# attinier84-motherboard-mk-2_0.net
KiCad netlist of a schematic drawn in EAGLE
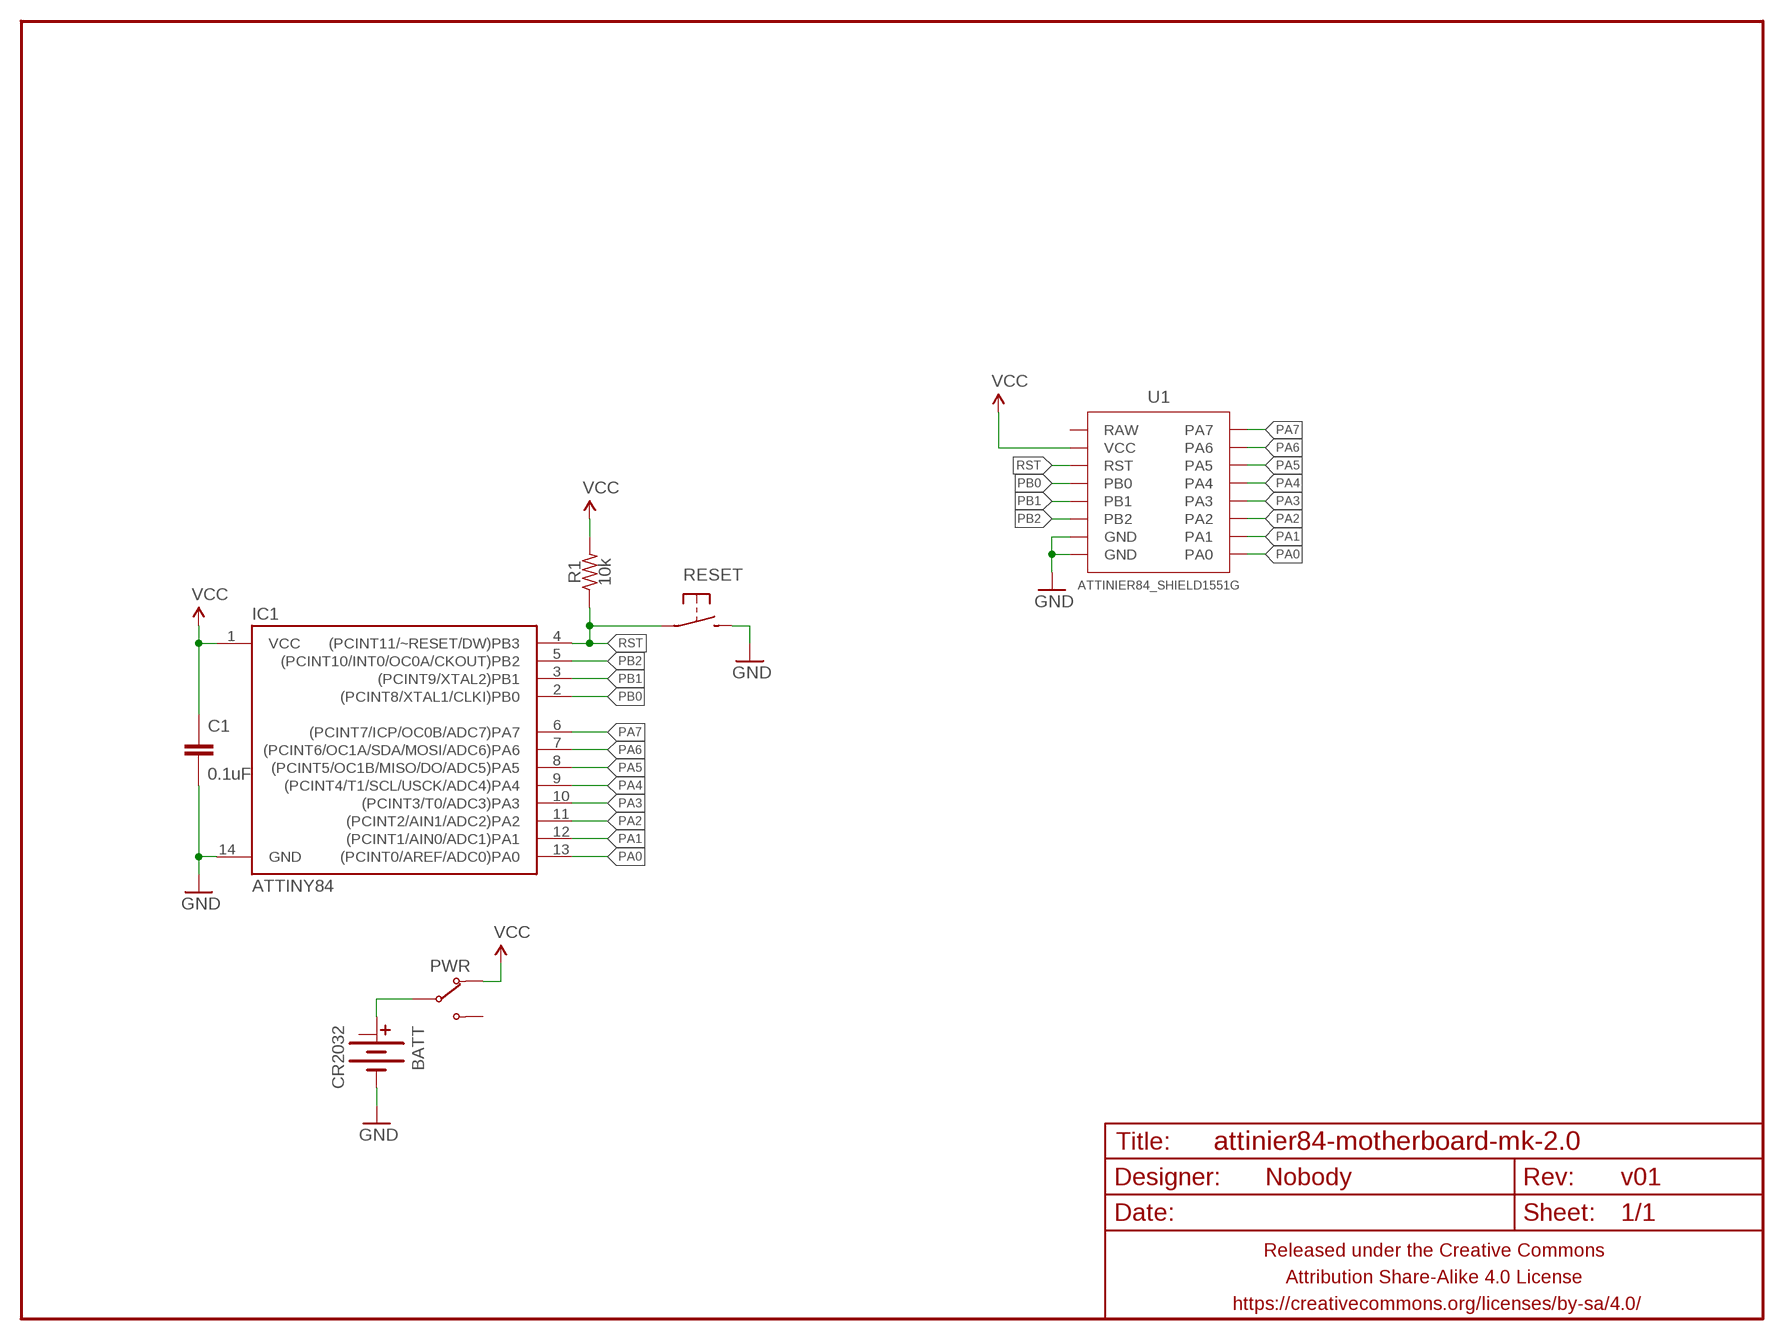
[diagram p0: schematic, sheet 1]

(export (version "E")
  (design (tool "Eeschema 10.0.6"))
  (components
    (comp (ref "BATT")
      (value "CR2032")
      (footprint "eagle-import:BATTCON_20MM_MINE")
      (libsource (lib "eagle-import") (part "BATTERY-COINCR2032_SMD"))
    )
    (comp (ref "C1")
      (value "0.1uF")
      (footprint "eagle-import:C0805")
      (libsource (lib "eagle-import") (part "CAPACITOR-CERAMICC0805"))
    )
    (comp (ref "FRAME1")
      (value "FRAME-LETTERNO_PACKAGE")
      (footprint "eagle-import:DUMMY")
      (fields (field (name "DESIGNER") "Nobody"))
      (libsource (lib "eagle-import") (part "FRAME-LETTERNO_PACKAGE"))
    )
    (comp (ref "IC1")
      (value "ATTINY84")
      (footprint "eagle-import:SO14")
      (libsource (lib "eagle-import") (part "ATTINY84"))
    )
    (comp (ref "PWR")
      (value "SWITCH-SPDTPTH-RA-2MM")
      (footprint "eagle-import:SPDT-RA-2MM")
      (libsource (lib "eagle-import") (part "SWITCH-SPDTPTH-RA-2MM"))
    )
    (comp (ref "R1")
      (value "10k")
      (footprint "eagle-import:R0805")
      (libsource (lib "eagle-import") (part "RESISTORR0805"))
    )
    (comp (ref "RESET")
      (value "SPST-NO-TACT6MM-SMD")
      (footprint "eagle-import:DTSM-6")
      (libsource (lib "eagle-import") (part "SPST-NO-TACT6MM-SMD"))
    )
    (comp (ref "U1")
      (value "ATTINIER84_SHIELD1551G")
      (footprint "eagle-import:ATTINIER84_SHIELD2")
      (libsource (lib "eagle-import") (part "ATTINIER84_SHIELD1551G"))
    )
  )
  (nets
    (net (code "1") (name "GND") (class "Default")
      (node (ref "BATT") (pin "BOTTOM") (pinfunction "-_BOTTOM") (pintype "bidirectional"))
      (node (ref "C1") (pin "2") (pinfunction "2_2") (pintype "passive"))
      (node (ref "IC1") (pin "14") (pinfunction "GND_14") (pintype "bidirectional"))
      (node (ref "RESET") (pin "3") (pinfunction "2_3") (pintype "passive"))
      (node (ref "RESET") (pin "4") (pinfunction "2_4") (pintype "passive"))
      (node (ref "U1") (pin "GND@1") (pinfunction "GND_GND@1") (pintype "bidirectional"))
      (node (ref "U1") (pin "GND@2") (pinfunction "GND_GND@2") (pintype "bidirectional"))
    )
    (net (code "2") (name "Net-(BATT-+)") (class "Default")
      (node (ref "BATT") (pin "TOP@1") (pinfunction "+_TOP@1") (pintype "bidirectional"))
      (node (ref "PWR") (pin "2") (pinfunction "COM_2") (pintype "passive"))
    )
    (net (code "3") (name "PA0") (class "Default")
      (node (ref "IC1") (pin "13") (pinfunction "(PCINT0/AREF/ADC0)PA0_13") (pintype "bidirectional"))
      (node (ref "U1") (pin "PA0") (pinfunction "PA0_PA0") (pintype "bidirectional"))
    )
    (net (code "4") (name "PA1") (class "Default")
      (node (ref "IC1") (pin "12") (pinfunction "(PCINT1/AIN0/ADC1)PA1_12") (pintype "bidirectional"))
      (node (ref "U1") (pin "PA1") (pinfunction "PA1_PA1") (pintype "bidirectional"))
    )
    (net (code "5") (name "PA2") (class "Default")
      (node (ref "IC1") (pin "11") (pinfunction "(PCINT2/AIN1/ADC2)PA2_11") (pintype "bidirectional"))
      (node (ref "U1") (pin "PA2") (pinfunction "PA2_PA2") (pintype "bidirectional"))
    )
    (net (code "6") (name "PA3") (class "Default")
      (node (ref "IC1") (pin "10") (pinfunction "(PCINT3/T0/ADC3)PA3_10") (pintype "bidirectional"))
      (node (ref "U1") (pin "PA3") (pinfunction "PA3_PA3") (pintype "bidirectional"))
    )
    (net (code "7") (name "PA4") (class "Default")
      (node (ref "IC1") (pin "9") (pinfunction "(PCINT4/T1/SCL/USCK/ADC4)PA4_9") (pintype "bidirectional"))
      (node (ref "U1") (pin "PA4") (pinfunction "PA4_PA4") (pintype "bidirectional"))
    )
    (net (code "8") (name "PA5") (class "Default")
      (node (ref "IC1") (pin "8") (pinfunction "(PCINT5/OC1B/MISO/DO/ADC5)PA5_8") (pintype "bidirectional"))
      (node (ref "U1") (pin "PA5") (pinfunction "PA5_PA5") (pintype "bidirectional"))
    )
    (net (code "9") (name "PA6") (class "Default")
      (node (ref "IC1") (pin "7") (pinfunction "(PCINT6/OC1A/SDA/MOSI/ADC6)PA6_7") (pintype "bidirectional"))
      (node (ref "U1") (pin "PA6") (pinfunction "PA6_PA6") (pintype "bidirectional"))
    )
    (net (code "10") (name "PA7") (class "Default")
      (node (ref "IC1") (pin "6") (pinfunction "(PCINT7/ICP/OC0B/ADC7)PA7_6") (pintype "bidirectional"))
      (node (ref "U1") (pin "PA7") (pinfunction "PA7_PA7") (pintype "bidirectional"))
    )
    (net (code "11") (name "PB0") (class "Default")
      (node (ref "IC1") (pin "2") (pinfunction "(PCINT8/XTAL1/CLKI)PB0_2") (pintype "bidirectional"))
      (node (ref "U1") (pin "PB0") (pinfunction "PB0_PB0") (pintype "bidirectional"))
    )
    (net (code "12") (name "PB1") (class "Default")
      (node (ref "IC1") (pin "3") (pinfunction "(PCINT9/XTAL2)PB1_3") (pintype "bidirectional"))
      (node (ref "U1") (pin "PB1") (pinfunction "PB1_PB1") (pintype "bidirectional"))
    )
    (net (code "13") (name "PB2") (class "Default")
      (node (ref "IC1") (pin "5") (pinfunction "(PCINT10/INT0/OC0A/CKOUT)PB2_5") (pintype "bidirectional"))
      (node (ref "U1") (pin "PB2") (pinfunction "PB2_PB2") (pintype "bidirectional"))
    )
    (net (code "14") (name "RST") (class "Default")
      (node (ref "IC1") (pin "4") (pinfunction "(PCINT11/~{RESET/DW})PB3_4") (pintype "bidirectional"))
      (node (ref "R1") (pin "1") (pinfunction "1_1") (pintype "passive"))
      (node (ref "RESET") (pin "1") (pinfunction "1_1") (pintype "passive"))
      (node (ref "RESET") (pin "2") (pinfunction "1_2") (pintype "passive"))
      (node (ref "U1") (pin "RST") (pinfunction "RST_RST") (pintype "bidirectional"))
    )
    (net (code "15") (name "VCC") (class "Default")
      (node (ref "C1") (pin "1") (pinfunction "1_1") (pintype "passive"))
      (node (ref "IC1") (pin "1") (pinfunction "VCC_1") (pintype "bidirectional"))
      (node (ref "PWR") (pin "1") (pinfunction "NC_1") (pintype "passive"))
      (node (ref "R1") (pin "2") (pinfunction "2_2") (pintype "passive"))
      (node (ref "U1") (pin "VCC") (pinfunction "VCC_VCC") (pintype "bidirectional"))
    )
    (net (code "16") (name "unconnected-(BATT-+1-PadTOP@2)") (class "Default")
      (node (ref "BATT") (pin "TOP@2") (pinfunction "+1_TOP@2") (pintype "bidirectional"))
    )
    (net (code "17") (name "unconnected-(PWR-NO-Pad3)") (class "Default")
      (node (ref "PWR") (pin "3") (pinfunction "NO_3") (pintype "passive"))
    )
    (net (code "18") (name "unconnected-(U1-PadRAW)") (class "Default")
      (node (ref "U1") (pin "RAW") (pinfunction "RAW_RAW") (pintype "bidirectional"))
    )
  )
)
